# PhaseShifter.net
KiCad netlist of a schematic drawn in Altium Designer
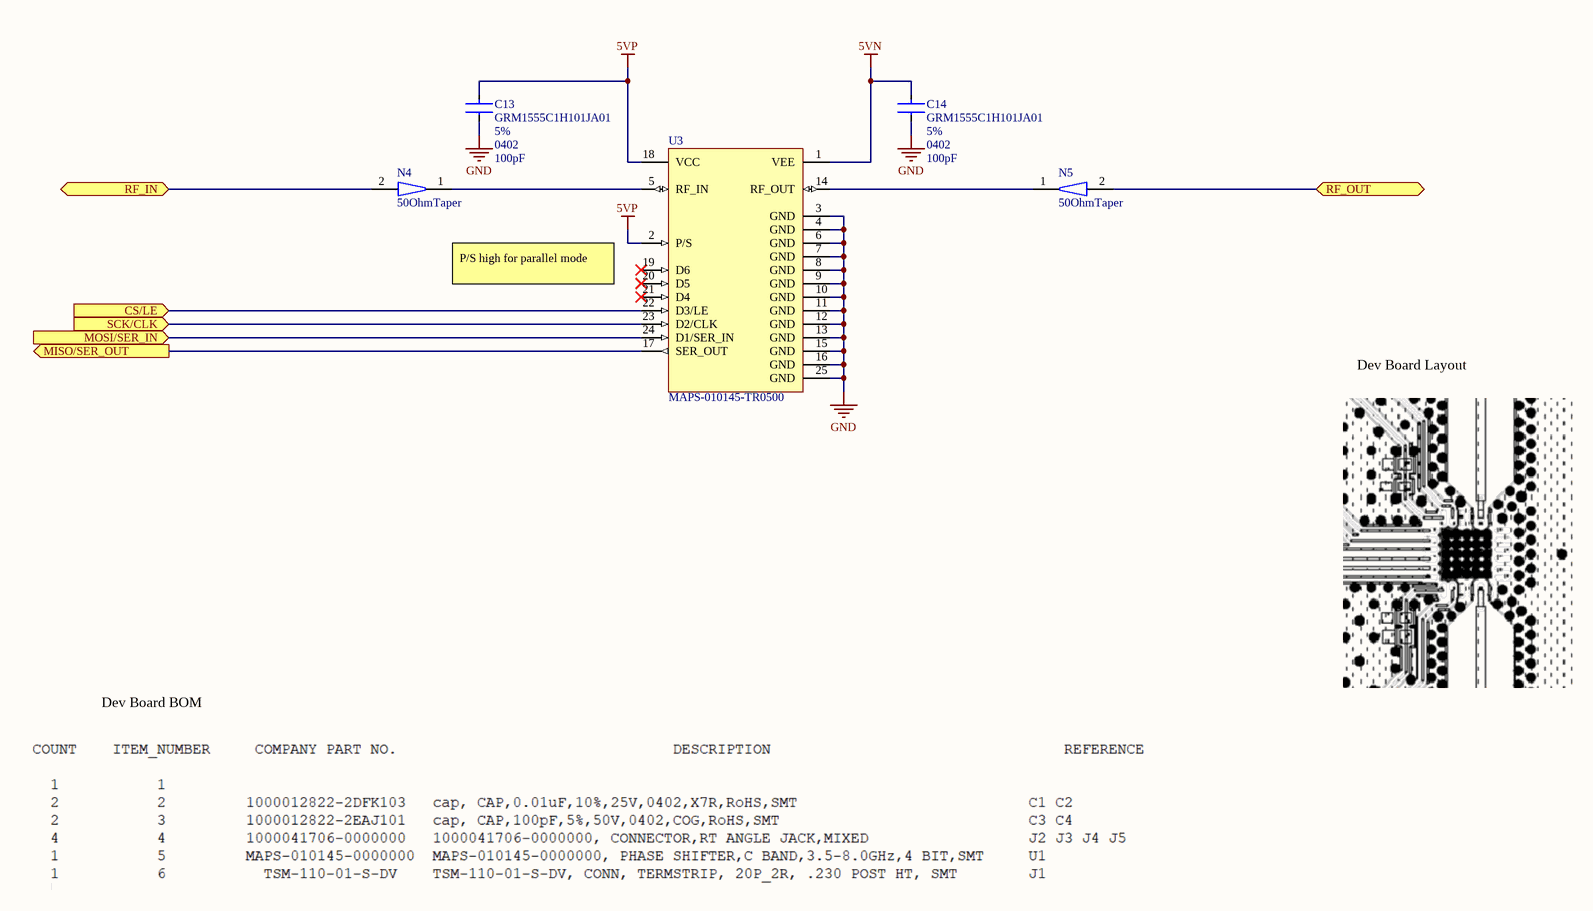
[diagram p0: PhaseShifter.SchDoc]

(export (version "E")
  (design (tool "Eeschema 10.0.6"))
  (components
    (comp (ref "C13")
      (value "GRM1555C1H101JA01")
      (footprint "Capacitor0402_Murata")
      (description "100 pF ±5% 50V Ceramic Capacitor C0G, NP0 0402 (1005 Metric)")
      (fields
        (field (name "TOLERANCE") "5%")
        (field (name "PACKAGE") "0402")
        (field (name "ALTIUM_VALUE") "100pF")
      )
      (libsource (lib "EECS430PhasedArray") (part "GRM1555C1H101JA01"))
    )
    (comp (ref "C14")
      (value "GRM1555C1H101JA01")
      (footprint "Capacitor0402_Murata")
      (description "100 pF ±5% 50V Ceramic Capacitor C0G, NP0 0402 (1005 Metric)")
      (fields
        (field (name "TOLERANCE") "5%")
        (field (name "PACKAGE") "0402")
        (field (name "ALTIUM_VALUE") "100pF")
      )
      (libsource (lib "EECS430PhasedArray") (part "GRM1555C1H101JA01"))
    )
    (comp (ref "N4")
      (value "50OhmTaper")
      (footprint "50OhmTaper")
      (description "Triangular taper from 50 Ohms to 0402 width")
      (libsource (lib "EECS430PhasedArray") (part "50OhmTaper"))
    )
    (comp (ref "N5")
      (value "50OhmTaper")
      (footprint "50OhmTaper")
      (description "Triangular taper from 50 Ohms to 0402 width")
      (libsource (lib "EECS430PhasedArray") (part "50OhmTaper"))
    )
    (comp (ref "U3")
      (value "MAPS-010145-TR0500")
      (footprint "MAPS-010145-TR0500_QFN50P400X400X100_HS-25N")
      (description "Phase Detectors / Shifters 3.5-6.0GHz 4-Bit Step 22.5 deg.")
      (libsource (lib "EECS430PhasedArray") (part "MAPS-010145-TR0500"))
    )
  )
  (nets
    (net (code "1") (name "/CS{slash}LE") (class "Default")
      (node (ref "U3") (pin "22") (pinfunction "D3/LE_22") (pintype "input"))
    )
    (net (code "2") (name "/MISO{slash}SER_OUT") (class "Default")
      (node (ref "U3") (pin "17") (pinfunction "SER_OUT_17") (pintype "output"))
    )
    (net (code "3") (name "/MOSI{slash}SER_IN") (class "Default")
      (node (ref "U3") (pin "24") (pinfunction "D1/SER_IN_24") (pintype "input"))
    )
    (net (code "4") (name "/RF_IN") (class "Default")
      (node (ref "N4") (pin "2") (pinfunction "2_2") (pintype "passive"))
    )
    (net (code "5") (name "/RF_OUT") (class "Default")
      (node (ref "N5") (pin "2") (pinfunction "2_2") (pintype "passive"))
    )
    (net (code "6") (name "/SCK{slash}CLK") (class "Default")
      (node (ref "U3") (pin "23") (pinfunction "D2/CLK_23") (pintype "input"))
    )
    (net (code "7") (name "5VN") (class "Default")
      (node (ref "C14") (pin "1") (pinfunction "1_1") (pintype "passive"))
      (node (ref "U3") (pin "1") (pinfunction "VEE_1") (pintype "power_in"))
    )
    (net (code "8") (name "5VP") (class "Default")
      (node (ref "C13") (pin "1") (pinfunction "1_1") (pintype "passive"))
      (node (ref "U3") (pin "18") (pinfunction "VCC_18") (pintype "power_in"))
      (node (ref "U3") (pin "2") (pinfunction "P/S_2") (pintype "input"))
    )
    (net (code "9") (name "GND") (class "Default")
      (node (ref "C13") (pin "2") (pinfunction "2_2") (pintype "passive"))
      (node (ref "C14") (pin "2") (pinfunction "2_2") (pintype "passive"))
      (node (ref "U3") (pin "10") (pinfunction "GND_10") (pintype "power_in"))
      (node (ref "U3") (pin "11") (pinfunction "GND_11") (pintype "power_in"))
      (node (ref "U3") (pin "12") (pinfunction "GND_12") (pintype "power_in"))
      (node (ref "U3") (pin "13") (pinfunction "GND_13") (pintype "power_in"))
      (node (ref "U3") (pin "15") (pinfunction "GND_15") (pintype "power_in"))
      (node (ref "U3") (pin "16") (pinfunction "GND_16") (pintype "power_in"))
      (node (ref "U3") (pin "25") (pinfunction "GND_25") (pintype "power_in"))
      (node (ref "U3") (pin "3") (pinfunction "GND_3") (pintype "power_in"))
      (node (ref "U3") (pin "4") (pinfunction "GND_4") (pintype "power_in"))
      (node (ref "U3") (pin "6") (pinfunction "GND_6") (pintype "power_in"))
      (node (ref "U3") (pin "7") (pinfunction "GND_7") (pintype "power_in"))
      (node (ref "U3") (pin "8") (pinfunction "GND_8") (pintype "power_in"))
      (node (ref "U3") (pin "9") (pinfunction "GND_9") (pintype "power_in"))
    )
    (net (code "10") (name "Net-(U3-RF_IN)") (class "Default")
      (node (ref "N4") (pin "1") (pinfunction "1_1") (pintype "passive"))
      (node (ref "U3") (pin "5") (pinfunction "RF_IN_5") (pintype "bidirectional"))
    )
    (net (code "11") (name "Net-(U3-RF_OUT)") (class "Default")
      (node (ref "N5") (pin "1") (pinfunction "1_1") (pintype "passive"))
      (node (ref "U3") (pin "14") (pinfunction "RF_OUT_14") (pintype "bidirectional"))
    )
    (net (code "12") (name "unconnected-(U3-D4-Pad21)") (class "Default")
      (node (ref "U3") (pin "21") (pinfunction "D4_21") (pintype "input+no_connect"))
    )
    (net (code "13") (name "unconnected-(U3-D5-Pad20)") (class "Default")
      (node (ref "U3") (pin "20") (pinfunction "D5_20") (pintype "input+no_connect"))
    )
    (net (code "14") (name "unconnected-(U3-D6-Pad19)") (class "Default")
      (node (ref "U3") (pin "19") (pinfunction "D6_19") (pintype "input+no_connect"))
    )
  )
)
